# mcuboard.net
KiCad netlist of a schematic drawn in EAGLE
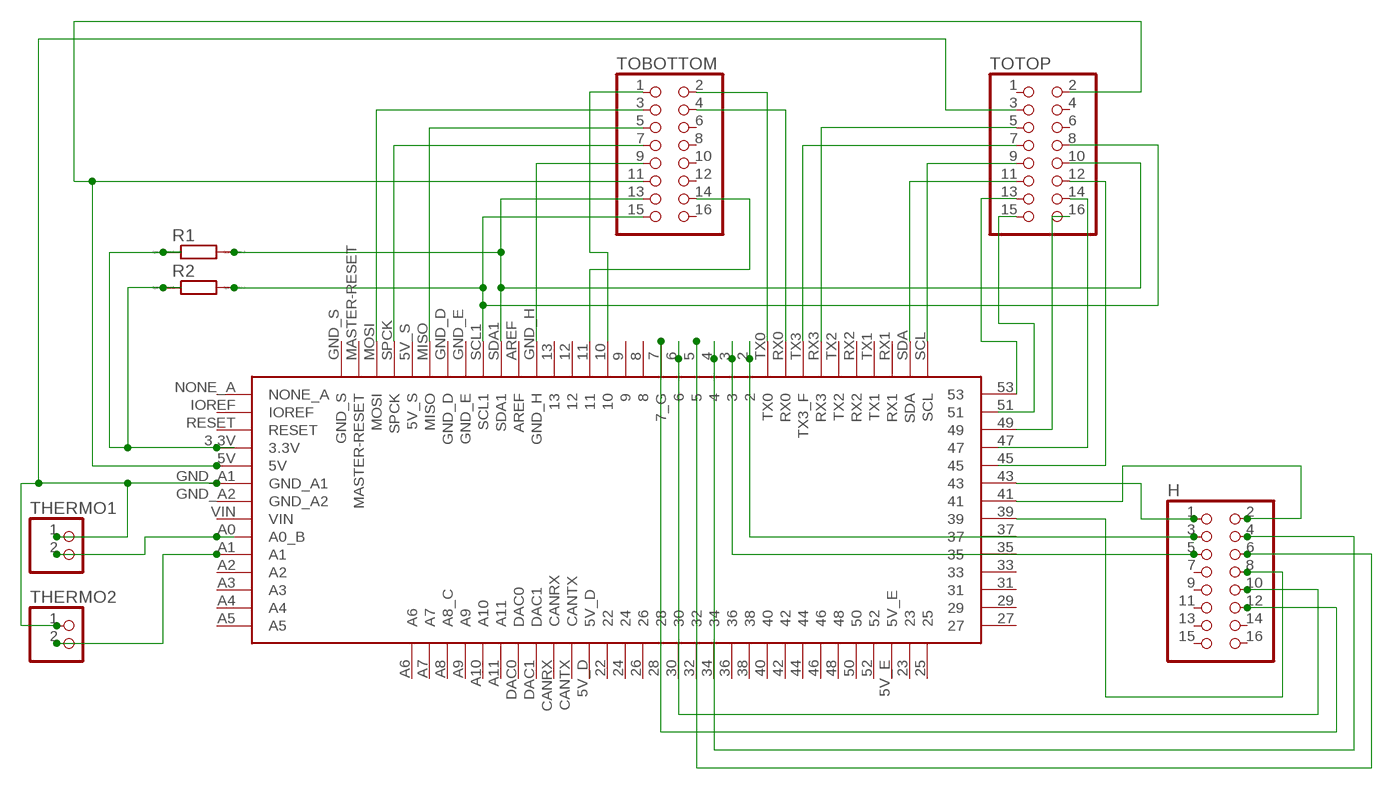
[diagram p0: schematic, sheet 1]

(export (version "E")
  (design (tool "Eeschema 10.0.6"))
  (components
    (comp (ref "H")
      (value "PINHD-2X8")
      (footprint "eagle-import:2X08")
      (libsource (lib "eagle-import") (part "PINHD-2X8"))
    )
    (comp (ref "R1")
      (value "R-EU_0207_12")
      (footprint "eagle-import:0207_12")
      (libsource (lib "eagle-import") (part "R-EU_0207_12"))
    )
    (comp (ref "R2")
      (value "R-EU_0207_12")
      (footprint "eagle-import:0207_12")
      (libsource (lib "eagle-import") (part "R-EU_0207_12"))
    )
    (comp (ref "THERMO1")
      (value "PINHD-1X2")
      (footprint "eagle-import:1X02")
      (libsource (lib "eagle-import") (part "PINHD-1X2"))
    )
    (comp (ref "THERMO2")
      (value "PINHD-1X2")
      (footprint "eagle-import:1X02")
      (libsource (lib "eagle-import") (part "PINHD-1X2"))
    )
    (comp (ref "TOBOTTOM")
      (value "PINHD-2X8")
      (footprint "eagle-import:2X08")
      (libsource (lib "eagle-import") (part "PINHD-2X8"))
    )
    (comp (ref "TOTOP")
      (value "PINHD-2X8")
      (footprint "eagle-import:2X08")
      (libsource (lib "eagle-import") (part "PINHD-2X8"))
    )
    (comp (ref "U$1")
      (value "IDUINO1")
      (footprint "eagle-import:IDUINO_PAC")
      (libsource (lib "eagle-import") (part "IDUINO1"))
    )
  )
  (nets
    (net (code "1") (name "Net-(H-Pad1)") (class "Default")
      (node (ref "H") (pin "1") (pinfunction "1_1") (pintype "passive"))
      (node (ref "U$1") (pin "43") (pinfunction "43_43") (pintype "bidirectional"))
    )
    (net (code "2") (name "Net-(H-Pad2)") (class "Default")
      (node (ref "H") (pin "2") (pinfunction "2_2") (pintype "passive"))
      (node (ref "U$1") (pin "41") (pinfunction "41_41") (pintype "bidirectional"))
    )
    (net (code "3") (name "Net-(H-Pad3)") (class "Default")
      (node (ref "H") (pin "3") (pinfunction "3_3") (pintype "passive"))
      (node (ref "U$1") (pin "2") (pinfunction "2_2") (pintype "bidirectional"))
    )
    (net (code "4") (name "Net-(H-Pad4)") (class "Default")
      (node (ref "H") (pin "4") (pinfunction "4_4") (pintype "passive"))
      (node (ref "U$1") (pin "4") (pinfunction "4_4") (pintype "bidirectional"))
    )
    (net (code "5") (name "Net-(H-Pad5)") (class "Default")
      (node (ref "H") (pin "5") (pinfunction "5_5") (pintype "passive"))
      (node (ref "U$1") (pin "3") (pinfunction "3_3") (pintype "bidirectional"))
    )
    (net (code "6") (name "Net-(H-Pad6)") (class "Default")
      (node (ref "H") (pin "6") (pinfunction "6_6") (pintype "passive"))
      (node (ref "U$1") (pin "5") (pinfunction "5_5") (pintype "bidirectional"))
    )
    (net (code "7") (name "Net-(H-Pad8)") (class "Default")
      (node (ref "H") (pin "8") (pinfunction "8_8") (pintype "passive"))
      (node (ref "U$1") (pin "39") (pinfunction "39_39") (pintype "bidirectional"))
    )
    (net (code "8") (name "Net-(H-Pad10)") (class "Default")
      (node (ref "H") (pin "10") (pinfunction "10_10") (pintype "passive"))
      (node (ref "U$1") (pin "6") (pinfunction "6_6") (pintype "bidirectional"))
    )
    (net (code "9") (name "Net-(R1-Pad1)") (class "Default")
      (node (ref "R1") (pin "1") (pinfunction "1_1") (pintype "passive"))
      (node (ref "R2") (pin "1") (pinfunction "1_1") (pintype "passive"))
      (node (ref "U$1") (pin "3.3V") (pinfunction "3.3V_3.3V") (pintype "bidirectional"))
    )
    (net (code "10") (name "Net-(R1-Pad2)") (class "Default")
      (node (ref "R1") (pin "2") (pinfunction "2_2") (pintype "passive"))
      (node (ref "TOBOTTOM") (pin "13") (pinfunction "13_13") (pintype "passive"))
      (node (ref "TOTOP") (pin "10") (pinfunction "10_10") (pintype "passive"))
      (node (ref "U$1") (pin "SDA1") (pinfunction "SDA1_SDA1") (pintype "bidirectional"))
    )
    (net (code "11") (name "Net-(R2-Pad2)") (class "Default")
      (node (ref "R2") (pin "2") (pinfunction "2_2") (pintype "passive"))
      (node (ref "TOBOTTOM") (pin "15") (pinfunction "15_15") (pintype "passive"))
      (node (ref "TOTOP") (pin "8") (pinfunction "8_8") (pintype "passive"))
      (node (ref "U$1") (pin "SCL1") (pinfunction "SCL1_SCL1") (pintype "bidirectional"))
    )
    (net (code "12") (name "Net-(THERMO1-Pad1)") (class "Default")
      (node (ref "THERMO1") (pin "1") (pinfunction "1_1") (pintype "passive"))
      (node (ref "THERMO2") (pin "1") (pinfunction "1_1") (pintype "passive"))
      (node (ref "TOTOP") (pin "3") (pinfunction "3_3") (pintype "passive"))
      (node (ref "U$1") (pin "GND_A1") (pinfunction "GND_A1_GND_A1") (pintype "bidirectional"))
    )
    (net (code "13") (name "Net-(THERMO2-Pad2)") (class "Default")
      (node (ref "THERMO2") (pin "2") (pinfunction "2_2") (pintype "passive"))
      (node (ref "U$1") (pin "A1") (pinfunction "A1_A1") (pintype "bidirectional"))
    )
    (net (code "14") (name "Net-(TOBOTTOM-Pad1)") (class "Default")
      (node (ref "TOBOTTOM") (pin "1") (pinfunction "1_1") (pintype "passive"))
      (node (ref "U$1") (pin "10") (pinfunction "10_10") (pintype "bidirectional"))
    )
    (net (code "15") (name "Net-(TOBOTTOM-Pad2)") (class "Default")
      (node (ref "TOBOTTOM") (pin "2") (pinfunction "2_2") (pintype "passive"))
      (node (ref "U$1") (pin "TX0") (pinfunction "TX0_TX0") (pintype "bidirectional"))
    )
    (net (code "16") (name "Net-(TOBOTTOM-Pad3)") (class "Default")
      (node (ref "TOBOTTOM") (pin "3") (pinfunction "3_3") (pintype "passive"))
      (node (ref "U$1") (pin "MOSI") (pinfunction "MOSI_MOSI") (pintype "bidirectional"))
    )
    (net (code "17") (name "Net-(TOBOTTOM-Pad4)") (class "Default")
      (node (ref "TOBOTTOM") (pin "4") (pinfunction "4_4") (pintype "passive"))
      (node (ref "U$1") (pin "RX0") (pinfunction "RX0_RX0") (pintype "bidirectional"))
    )
    (net (code "18") (name "Net-(TOBOTTOM-Pad5)") (class "Default")
      (node (ref "TOBOTTOM") (pin "5") (pinfunction "5_5") (pintype "passive"))
      (node (ref "U$1") (pin "MISO") (pinfunction "MISO_MISO") (pintype "bidirectional"))
    )
    (net (code "19") (name "Net-(TOBOTTOM-Pad7)") (class "Default")
      (node (ref "TOBOTTOM") (pin "7") (pinfunction "7_7") (pintype "passive"))
      (node (ref "U$1") (pin "SPCK") (pinfunction "SPCK_SPCK") (pintype "bidirectional"))
    )
    (net (code "20") (name "Net-(TOBOTTOM-Pad9)") (class "Default")
      (node (ref "TOBOTTOM") (pin "9") (pinfunction "9_9") (pintype "passive"))
      (node (ref "U$1") (pin "GND_H") (pinfunction "GND_H_GND_H") (pintype "bidirectional"))
    )
    (net (code "21") (name "Net-(TOBOTTOM-Pad11)") (class "Default")
      (node (ref "TOBOTTOM") (pin "11") (pinfunction "11_11") (pintype "passive"))
      (node (ref "TOTOP") (pin "2") (pinfunction "2_2") (pintype "passive"))
      (node (ref "U$1") (pin "5V") (pinfunction "5V_5V") (pintype "bidirectional"))
    )
    (net (code "22") (name "Net-(TOBOTTOM-Pad14)") (class "Default")
      (node (ref "TOBOTTOM") (pin "14") (pinfunction "14_14") (pintype "passive"))
      (node (ref "U$1") (pin "11") (pinfunction "11_11") (pintype "bidirectional"))
    )
    (net (code "23") (name "Net-(TOTOP-Pad5)") (class "Default")
      (node (ref "TOTOP") (pin "5") (pinfunction "5_5") (pintype "passive"))
      (node (ref "U$1") (pin "RX3") (pinfunction "RX3_RX3") (pintype "bidirectional"))
    )
    (net (code "24") (name "Net-(TOTOP-Pad9)") (class "Default")
      (node (ref "TOTOP") (pin "9") (pinfunction "9_9") (pintype "passive"))
      (node (ref "U$1") (pin "SCL") (pinfunction "SCL_SCL") (pintype "bidirectional"))
    )
    (net (code "25") (name "Net-(TOTOP-Pad11)") (class "Default")
      (node (ref "TOTOP") (pin "11") (pinfunction "11_11") (pintype "passive"))
      (node (ref "U$1") (pin "SDA") (pinfunction "SDA_SDA") (pintype "bidirectional"))
    )
    (net (code "26") (name "Net-(TOTOP-Pad13)") (class "Default")
      (node (ref "TOTOP") (pin "13") (pinfunction "13_13") (pintype "passive"))
      (node (ref "U$1") (pin "53") (pinfunction "53_53") (pintype "bidirectional"))
    )
    (net (code "27") (name "Net-(TOTOP-Pad16)") (class "Default")
      (node (ref "TOTOP") (pin "16") (pinfunction "16_16") (pintype "passive"))
      (node (ref "U$1") (pin "49") (pinfunction "49_49") (pintype "bidirectional"))
    )
    (net (code "28") (name "Net-(U$1-7_G)") (class "Default")
      (node (ref "H") (pin "12") (pinfunction "12_12") (pintype "passive"))
      (node (ref "U$1") (pin "7") (pinfunction "7_G_7") (pintype "bidirectional"))
    )
    (net (code "29") (name "Net-(U$1-A0_B)") (class "Default")
      (node (ref "THERMO1") (pin "2") (pinfunction "2_2") (pintype "passive"))
      (node (ref "U$1") (pin "A0") (pinfunction "A0_B_A0") (pintype "bidirectional"))
    )
    (net (code "30") (name "Net-(U$1-TX3_F)") (class "Default")
      (node (ref "TOTOP") (pin "7") (pinfunction "7_7") (pintype "passive"))
      (node (ref "U$1") (pin "TX3") (pinfunction "TX3_F_TX3") (pintype "bidirectional"))
    )
    (net (code "31") (name "unconnected-(H-Pad7)") (class "Default")
      (node (ref "H") (pin "7") (pinfunction "7_7") (pintype "passive"))
    )
    (net (code "32") (name "unconnected-(H-Pad9)") (class "Default")
      (node (ref "H") (pin "9") (pinfunction "9_9") (pintype "passive"))
    )
    (net (code "33") (name "unconnected-(H-Pad11)") (class "Default")
      (node (ref "H") (pin "11") (pinfunction "11_11") (pintype "passive"))
    )
    (net (code "34") (name "unconnected-(H-Pad13)") (class "Default")
      (node (ref "H") (pin "13") (pinfunction "13_13") (pintype "passive"))
    )
    (net (code "35") (name "unconnected-(H-Pad14)") (class "Default")
      (node (ref "H") (pin "14") (pinfunction "14_14") (pintype "passive"))
    )
    (net (code "36") (name "unconnected-(H-Pad15)") (class "Default")
      (node (ref "H") (pin "15") (pinfunction "15_15") (pintype "passive"))
    )
    (net (code "37") (name "unconnected-(H-Pad16)") (class "Default")
      (node (ref "H") (pin "16") (pinfunction "16_16") (pintype "passive"))
    )
    (net (code "38") (name "unconnected-(TOBOTTOM-Pad6)") (class "Default")
      (node (ref "TOBOTTOM") (pin "6") (pinfunction "6_6") (pintype "passive"))
    )
    (net (code "39") (name "unconnected-(TOBOTTOM-Pad8)") (class "Default")
      (node (ref "TOBOTTOM") (pin "8") (pinfunction "8_8") (pintype "passive"))
    )
    (net (code "40") (name "unconnected-(TOBOTTOM-Pad10)") (class "Default")
      (node (ref "TOBOTTOM") (pin "10") (pinfunction "10_10") (pintype "passive"))
    )
    (net (code "41") (name "unconnected-(TOBOTTOM-Pad12)") (class "Default")
      (node (ref "TOBOTTOM") (pin "12") (pinfunction "12_12") (pintype "passive"))
    )
    (net (code "42") (name "unconnected-(TOBOTTOM-Pad16)") (class "Default")
      (node (ref "TOBOTTOM") (pin "16") (pinfunction "16_16") (pintype "passive"))
    )
    (net (code "43") (name "unconnected-(TOTOP-Pad1)") (class "Default")
      (node (ref "TOTOP") (pin "1") (pinfunction "1_1") (pintype "passive"))
    )
    (net (code "44") (name "unconnected-(TOTOP-Pad4)") (class "Default")
      (node (ref "TOTOP") (pin "4") (pinfunction "4_4") (pintype "passive"))
    )
    (net (code "45") (name "unconnected-(TOTOP-Pad6)") (class "Default")
      (node (ref "TOTOP") (pin "6") (pinfunction "6_6") (pintype "passive"))
    )
    (net (code "46") (name "unconnected-(TOTOP-Pad12)") (class "Default")
      (node (ref "TOTOP") (pin "12") (pinfunction "12_12") (pintype "passive"))
    )
    (net (code "47") (name "unconnected-(TOTOP-Pad14)") (class "Default")
      (node (ref "TOTOP") (pin "14") (pinfunction "14_14") (pintype "passive"))
    )
    (net (code "48") (name "unconnected-(TOTOP-Pad15)") (class "Default")
      (node (ref "TOTOP") (pin "15") (pinfunction "15_15") (pintype "passive"))
    )
    (net (code "49") (name "unconnected-(U$1-A8_C-PadA8)") (class "Default")
      (node (ref "U$1") (pin "A8") (pinfunction "A8_C_A8") (pintype "bidirectional"))
    )
    (net (code "50") (name "unconnected-(U$1-Pad5V_D)") (class "Default")
      (node (ref "U$1") (pin "5V_D") (pinfunction "5V_D_5V_D") (pintype "bidirectional"))
    )
    (net (code "51") (name "unconnected-(U$1-Pad5V_E)") (class "Default")
      (node (ref "U$1") (pin "5V_E") (pinfunction "5V_E_5V_E") (pintype "bidirectional"))
    )
    (net (code "52") (name "unconnected-(U$1-Pad5V_S)") (class "Default")
      (node (ref "U$1") (pin "5V_S") (pinfunction "5V_S_5V_S") (pintype "bidirectional"))
    )
    (net (code "53") (name "unconnected-(U$1-Pad8)") (class "Default")
      (node (ref "U$1") (pin "8") (pinfunction "8_8") (pintype "bidirectional"))
    )
    (net (code "54") (name "unconnected-(U$1-Pad9)") (class "Default")
      (node (ref "U$1") (pin "9") (pinfunction "9_9") (pintype "bidirectional"))
    )
    (net (code "55") (name "unconnected-(U$1-Pad12)") (class "Default")
      (node (ref "U$1") (pin "12") (pinfunction "12_12") (pintype "bidirectional"))
    )
    (net (code "56") (name "unconnected-(U$1-Pad13)") (class "Default")
      (node (ref "U$1") (pin "13") (pinfunction "13_13") (pintype "bidirectional"))
    )
    (net (code "57") (name "unconnected-(U$1-Pad22)") (class "Default")
      (node (ref "U$1") (pin "22") (pinfunction "22_22") (pintype "bidirectional"))
    )
    (net (code "58") (name "unconnected-(U$1-Pad23)") (class "Default")
      (node (ref "U$1") (pin "23") (pinfunction "23_23") (pintype "bidirectional"))
    )
    (net (code "59") (name "unconnected-(U$1-Pad24)") (class "Default")
      (node (ref "U$1") (pin "24") (pinfunction "24_24") (pintype "bidirectional"))
    )
    (net (code "60") (name "unconnected-(U$1-Pad25)") (class "Default")
      (node (ref "U$1") (pin "25") (pinfunction "25_25") (pintype "bidirectional"))
    )
    (net (code "61") (name "unconnected-(U$1-Pad26)") (class "Default")
      (node (ref "U$1") (pin "26") (pinfunction "26_26") (pintype "bidirectional"))
    )
    (net (code "62") (name "unconnected-(U$1-Pad27)") (class "Default")
      (node (ref "U$1") (pin "27") (pinfunction "27_27") (pintype "bidirectional"))
    )
    (net (code "63") (name "unconnected-(U$1-Pad28)") (class "Default")
      (node (ref "U$1") (pin "28") (pinfunction "28_28") (pintype "bidirectional"))
    )
    (net (code "64") (name "unconnected-(U$1-Pad29)") (class "Default")
      (node (ref "U$1") (pin "29") (pinfunction "29_29") (pintype "bidirectional"))
    )
    (net (code "65") (name "unconnected-(U$1-Pad30)") (class "Default")
      (node (ref "U$1") (pin "30") (pinfunction "30_30") (pintype "bidirectional"))
    )
    (net (code "66") (name "unconnected-(U$1-Pad31)") (class "Default")
      (node (ref "U$1") (pin "31") (pinfunction "31_31") (pintype "bidirectional"))
    )
    (net (code "67") (name "unconnected-(U$1-Pad32)") (class "Default")
      (node (ref "U$1") (pin "32") (pinfunction "32_32") (pintype "bidirectional"))
    )
    (net (code "68") (name "unconnected-(U$1-Pad33)") (class "Default")
      (node (ref "U$1") (pin "33") (pinfunction "33_33") (pintype "bidirectional"))
    )
    (net (code "69") (name "unconnected-(U$1-Pad34)") (class "Default")
      (node (ref "U$1") (pin "34") (pinfunction "34_34") (pintype "bidirectional"))
    )
    (net (code "70") (name "unconnected-(U$1-Pad35)") (class "Default")
      (node (ref "U$1") (pin "35") (pinfunction "35_35") (pintype "bidirectional"))
    )
    (net (code "71") (name "unconnected-(U$1-Pad36)") (class "Default")
      (node (ref "U$1") (pin "36") (pinfunction "36_36") (pintype "bidirectional"))
    )
    (net (code "72") (name "unconnected-(U$1-Pad37)") (class "Default")
      (node (ref "U$1") (pin "37") (pinfunction "37_37") (pintype "bidirectional"))
    )
    (net (code "73") (name "unconnected-(U$1-Pad38)") (class "Default")
      (node (ref "U$1") (pin "38") (pinfunction "38_38") (pintype "bidirectional"))
    )
    (net (code "74") (name "unconnected-(U$1-Pad40)") (class "Default")
      (node (ref "U$1") (pin "40") (pinfunction "40_40") (pintype "bidirectional"))
    )
    (net (code "75") (name "unconnected-(U$1-Pad42)") (class "Default")
      (node (ref "U$1") (pin "42") (pinfunction "42_42") (pintype "bidirectional"))
    )
    (net (code "76") (name "unconnected-(U$1-Pad44)") (class "Default")
      (node (ref "U$1") (pin "44") (pinfunction "44_44") (pintype "bidirectional"))
    )
    (net (code "77") (name "unconnected-(U$1-Pad45)") (class "Default")
      (node (ref "U$1") (pin "45") (pinfunction "45_45") (pintype "bidirectional"))
    )
    (net (code "78") (name "unconnected-(U$1-Pad46)") (class "Default")
      (node (ref "U$1") (pin "46") (pinfunction "46_46") (pintype "bidirectional"))
    )
    (net (code "79") (name "unconnected-(U$1-Pad47)") (class "Default")
      (node (ref "U$1") (pin "47") (pinfunction "47_47") (pintype "bidirectional"))
    )
    (net (code "80") (name "unconnected-(U$1-Pad48)") (class "Default")
      (node (ref "U$1") (pin "48") (pinfunction "48_48") (pintype "bidirectional"))
    )
    (net (code "81") (name "unconnected-(U$1-Pad50)") (class "Default")
      (node (ref "U$1") (pin "50") (pinfunction "50_50") (pintype "bidirectional"))
    )
    (net (code "82") (name "unconnected-(U$1-Pad51)") (class "Default")
      (node (ref "U$1") (pin "51") (pinfunction "51_51") (pintype "bidirectional"))
    )
    (net (code "83") (name "unconnected-(U$1-Pad52)") (class "Default")
      (node (ref "U$1") (pin "52") (pinfunction "52_52") (pintype "bidirectional"))
    )
    (net (code "84") (name "unconnected-(U$1-PadA2)") (class "Default")
      (node (ref "U$1") (pin "A2") (pinfunction "A2_A2") (pintype "bidirectional"))
    )
    (net (code "85") (name "unconnected-(U$1-PadA3)") (class "Default")
      (node (ref "U$1") (pin "A3") (pinfunction "A3_A3") (pintype "bidirectional"))
    )
    (net (code "86") (name "unconnected-(U$1-PadA4)") (class "Default")
      (node (ref "U$1") (pin "A4") (pinfunction "A4_A4") (pintype "bidirectional"))
    )
    (net (code "87") (name "unconnected-(U$1-PadA5)") (class "Default")
      (node (ref "U$1") (pin "A5") (pinfunction "A5_A5") (pintype "bidirectional"))
    )
    (net (code "88") (name "unconnected-(U$1-PadA6)") (class "Default")
      (node (ref "U$1") (pin "A6") (pinfunction "A6_A6") (pintype "bidirectional"))
    )
    (net (code "89") (name "unconnected-(U$1-PadA7)") (class "Default")
      (node (ref "U$1") (pin "A7") (pinfunction "A7_A7") (pintype "bidirectional"))
    )
    (net (code "90") (name "unconnected-(U$1-PadA9)") (class "Default")
      (node (ref "U$1") (pin "A9") (pinfunction "A9_A9") (pintype "bidirectional"))
    )
    (net (code "91") (name "unconnected-(U$1-PadA10)") (class "Default")
      (node (ref "U$1") (pin "A10") (pinfunction "A10_A10") (pintype "bidirectional"))
    )
    (net (code "92") (name "unconnected-(U$1-PadA11)") (class "Default")
      (node (ref "U$1") (pin "A11") (pinfunction "A11_A11") (pintype "bidirectional"))
    )
    (net (code "93") (name "unconnected-(U$1-PadAREF)") (class "Default")
      (node (ref "U$1") (pin "AREF") (pinfunction "AREF_AREF") (pintype "bidirectional"))
    )
    (net (code "94") (name "unconnected-(U$1-PadCANRX)") (class "Default")
      (node (ref "U$1") (pin "CANRX") (pinfunction "CANRX_CANRX") (pintype "bidirectional"))
    )
    (net (code "95") (name "unconnected-(U$1-PadCANTX)") (class "Default")
      (node (ref "U$1") (pin "CANTX") (pinfunction "CANTX_CANTX") (pintype "bidirectional"))
    )
    (net (code "96") (name "unconnected-(U$1-PadDAC0)") (class "Default")
      (node (ref "U$1") (pin "DAC0") (pinfunction "DAC0_DAC0") (pintype "bidirectional"))
    )
    (net (code "97") (name "unconnected-(U$1-PadDAC1)") (class "Default")
      (node (ref "U$1") (pin "DAC1") (pinfunction "DAC1_DAC1") (pintype "bidirectional"))
    )
    (net (code "98") (name "unconnected-(U$1-PadGND_A2)") (class "Default")
      (node (ref "U$1") (pin "GND_A2") (pinfunction "GND_A2_GND_A2") (pintype "bidirectional"))
    )
    (net (code "99") (name "unconnected-(U$1-PadGND_D)") (class "Default")
      (node (ref "U$1") (pin "GND_D") (pinfunction "GND_D_GND_D") (pintype "bidirectional"))
    )
    (net (code "100") (name "unconnected-(U$1-PadGND_E)") (class "Default")
      (node (ref "U$1") (pin "GND_E") (pinfunction "GND_E_GND_E") (pintype "bidirectional"))
    )
    (net (code "101") (name "unconnected-(U$1-PadGND_S)") (class "Default")
      (node (ref "U$1") (pin "GND_S") (pinfunction "GND_S_GND_S") (pintype "bidirectional"))
    )
    (net (code "102") (name "unconnected-(U$1-PadIOREF)") (class "Default")
      (node (ref "U$1") (pin "IOREF") (pinfunction "IOREF_IOREF") (pintype "bidirectional"))
    )
    (net (code "103") (name "unconnected-(U$1-PadMASTER-RESET)") (class "Default")
      (node (ref "U$1") (pin "MASTER-RESET") (pinfunction "MASTER-RESET_MASTER-RESET") (pintype "bidirectional"))
    )
    (net (code "104") (name "unconnected-(U$1-PadNONE_A)") (class "Default")
      (node (ref "U$1") (pin "NONE_A") (pinfunction "NONE_A_NONE_A") (pintype "bidirectional"))
    )
    (net (code "105") (name "unconnected-(U$1-PadRESET)") (class "Default")
      (node (ref "U$1") (pin "RESET") (pinfunction "RESET_RESET") (pintype "bidirectional"))
    )
    (net (code "106") (name "unconnected-(U$1-PadRX1)") (class "Default")
      (node (ref "U$1") (pin "RX1") (pinfunction "RX1_RX1") (pintype "bidirectional"))
    )
    (net (code "107") (name "unconnected-(U$1-PadRX2)") (class "Default")
      (node (ref "U$1") (pin "RX2") (pinfunction "RX2_RX2") (pintype "bidirectional"))
    )
    (net (code "108") (name "unconnected-(U$1-PadTX1)") (class "Default")
      (node (ref "U$1") (pin "TX1") (pinfunction "TX1_TX1") (pintype "bidirectional"))
    )
    (net (code "109") (name "unconnected-(U$1-PadTX2)") (class "Default")
      (node (ref "U$1") (pin "TX2") (pinfunction "TX2_TX2") (pintype "bidirectional"))
    )
    (net (code "110") (name "unconnected-(U$1-PadVIN)") (class "Default")
      (node (ref "U$1") (pin "VIN") (pinfunction "VIN_VIN") (pintype "bidirectional"))
    )
  )
)
